# typical-circuit.net
KiCad netlist of a schematic drawn in EAGLE
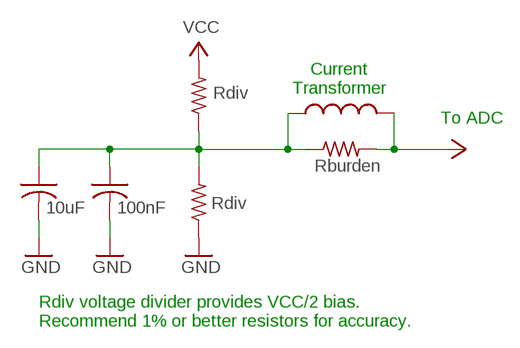
[diagram p0: schematic, sheet 1]

(export (version "E")
  (design (tool "Eeschema 10.0.6"))
  (components
    (comp (ref "C1")
      (value "10uF")
      (footprint "eagle-import:M0805")
      (libsource (lib "eagle-import") (part "C-USM0805"))
    )
    (comp (ref "C2")
      (value "100nF")
      (footprint "eagle-import:M0805")
      (libsource (lib "eagle-import") (part "C-USM0805"))
    )
    (comp (ref "L1")
      (value "L-USTJ3-U2")
      (footprint "eagle-import:TJ3-U2")
      (libsource (lib "eagle-import") (part "L-USTJ3-U2"))
    )
    (comp (ref "R1")
      (value "Rdiv")
      (footprint "eagle-import:M0805")
      (libsource (lib "eagle-import") (part "R-US_M0805"))
    )
    (comp (ref "R2")
      (value "Rdiv")
      (footprint "eagle-import:M0805")
      (libsource (lib "eagle-import") (part "R-US_M0805"))
    )
    (comp (ref "R3")
      (value "Rburden")
      (footprint "eagle-import:M0805")
      (libsource (lib "eagle-import") (part "R-US_M0805"))
    )
  )
  (nets
    (net (code "1") (name "GND") (class "Default")
      (node (ref "C1") (pin "2") (pinfunction "2_2") (pintype "passive"))
      (node (ref "C2") (pin "2") (pinfunction "2_2") (pintype "passive"))
      (node (ref "R1") (pin "1") (pinfunction "1_1") (pintype "passive"))
    )
    (net (code "2") (name "Net-(C1-Pad1)") (class "Default")
      (node (ref "C1") (pin "1") (pinfunction "1_1") (pintype "passive"))
      (node (ref "C2") (pin "1") (pinfunction "1_1") (pintype "passive"))
      (node (ref "L1") (pin "1") (pinfunction "1_1") (pintype "passive"))
      (node (ref "R1") (pin "2") (pinfunction "2_2") (pintype "passive"))
      (node (ref "R2") (pin "1") (pinfunction "1_1") (pintype "passive"))
      (node (ref "R3") (pin "1") (pinfunction "1_1") (pintype "passive"))
    )
    (net (code "3") (name "VCC") (class "Default")
      (node (ref "L1") (pin "2") (pinfunction "2_2") (pintype "passive"))
      (node (ref "R2") (pin "2") (pinfunction "2_2") (pintype "passive"))
      (node (ref "R3") (pin "2") (pinfunction "2_2") (pintype "passive"))
    )
  )
)
